# Acquisition-System_HMI_V1_0.net
KiCad netlist of a schematic drawn in Altium Designer
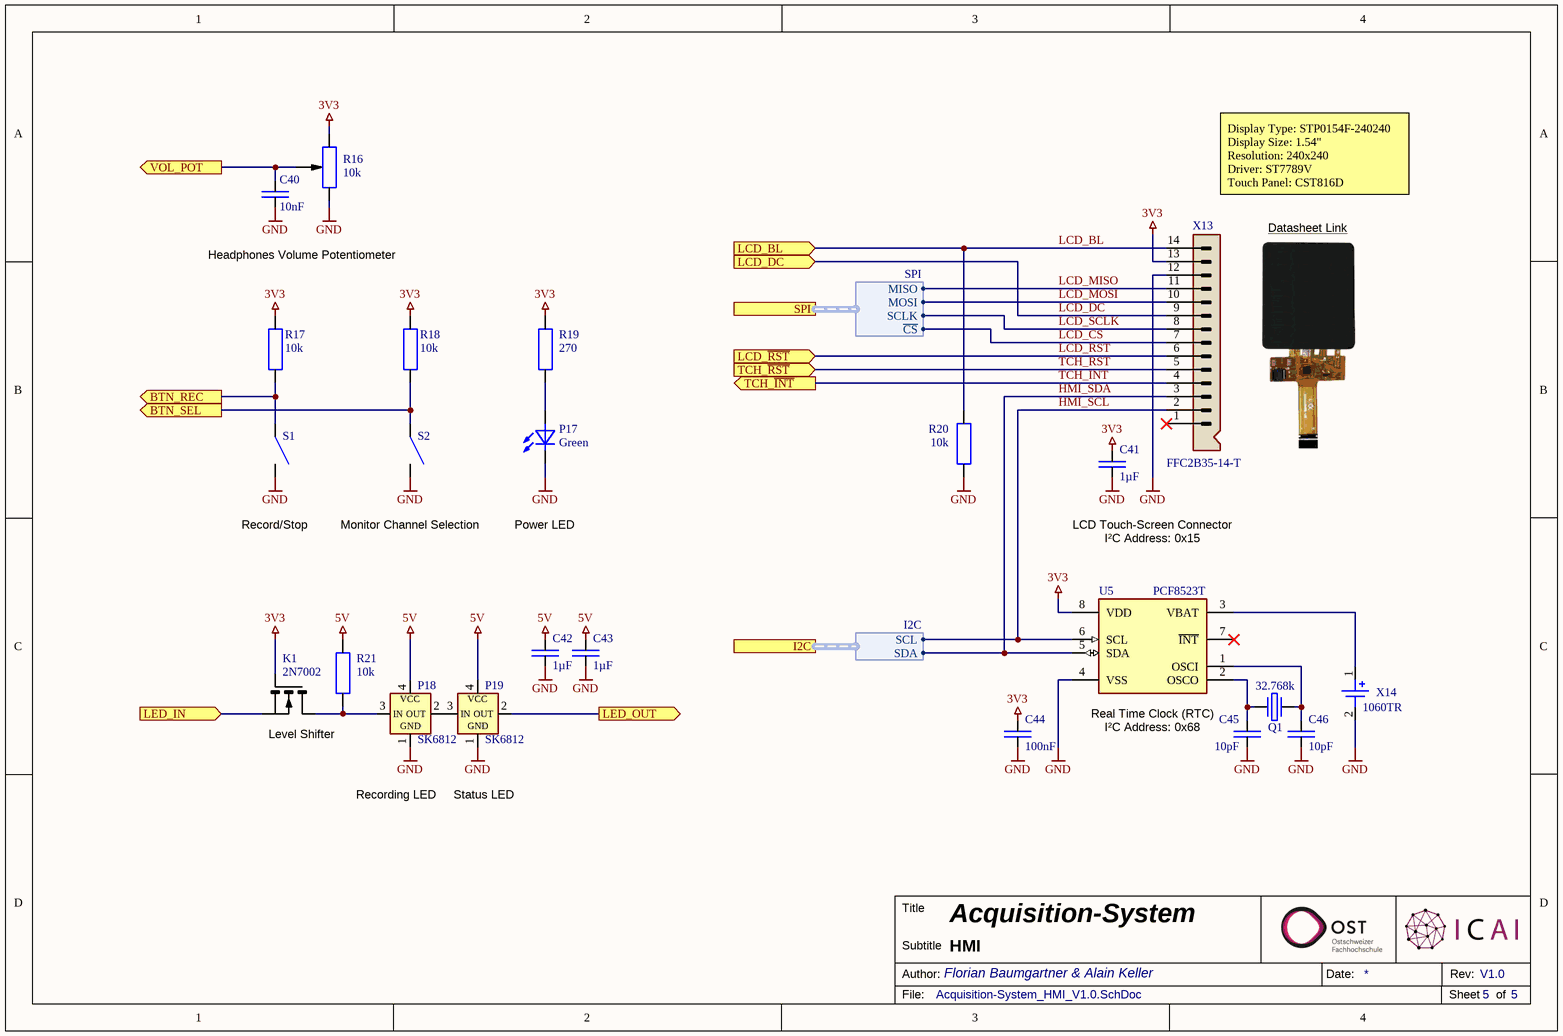
[diagram p0: Acquisition-System_HMI_V1.0.SchDoc]

(export (version "E")
  (design (tool "Eeschema 10.0.6"))
  (components
    (comp (ref "C40")
      (value "10nF")
      (footprint "SMD Keramikkondensator 0603")
      (description "CAP-MK")
      (libsource (lib "AudioAmp") (part "C-CAPACITOR"))
    )
    (comp (ref "C41")
      (value "1µF")
      (footprint "SMD Keramikkondensator 0603")
      (description "CAP-MK")
      (libsource (lib "AudioAmp") (part "C-CAPACITOR"))
    )
    (comp (ref "C42")
      (value "1µF")
      (footprint "SMD Keramikkondensator 0603")
      (description "CAP-MK")
      (libsource (lib "AudioAmp") (part "C-CAPACITOR"))
    )
    (comp (ref "C43")
      (value "1µF")
      (footprint "SMD Keramikkondensator 0603")
      (description "CAP-MK")
      (libsource (lib "AudioAmp") (part "C-CAPACITOR"))
    )
    (comp (ref "C44")
      (value "100nF")
      (footprint "SMD Keramikkondensator 0603")
      (description "SMD Ceramic Capacitor E6")
      (libsource (lib "Ceramic Capacitors-E6") (part "E6 - 100nF"))
    )
    (comp (ref "C45")
      (value "10pF")
      (footprint "SMD Keramikkondensator 0603")
      (description "CAP-MK")
      (libsource (lib "AudioAmp") (part "C-CAPACITOR"))
    )
    (comp (ref "C46")
      (value "10pF")
      (footprint "SMD Keramikkondensator 0603")
      (description "CAP-MK")
      (libsource (lib "AudioAmp") (part "C-CAPACITOR"))
    )
    (comp (ref "K1")
      (value "2N7002")
      (footprint "SMD MOSFET SOT-23")
      (description "MOSFET N-Channel")
      (libsource (lib "Nixie-Test") (part "K-FET{colon}NIGE"))
    )
    (comp (ref "P17")
      (value "Green")
      (footprint "SMD LED 0603")
      (description "General Purpose LED")
      (libsource (lib "Fleet-Monitor") (part "LED Green 0603"))
    )
    (comp (ref "P18")
      (value "SK6812")
      (footprint "SMD LED WS2812B-3528")
      (description "Smart RGB-LED")
      (libsource (lib "Acquisition-System") (part "P-SK6812D-EC3210R"))
    )
    (comp (ref "P19")
      (value "SK6812")
      (footprint "SMD LED WS2812B-3528")
      (description "Smart RGB-LED")
      (libsource (lib "Acquisition-System") (part "P-SK6812D-EC3210R"))
    )
    (comp (ref "Q1") (value "32.768k") (libsource (lib "Acquisition-System") (part "Q-Crystal")))
    (comp (ref "R16")
      (value "10k")
      (footprint "THT Potentiometer (RK09D1130C2P)")
      (description "RES-VAR")
      (libsource (lib "Acquisition-System") (part "R-RES{colon}VAR"))
    )
    (comp (ref "R17")
      (value "10k")
      (footprint "SMD Widerstand 0603")
      (description "RES (E=Heizwiderstand B=Messwandler)")
      (libsource (lib "TFS Integrated Library") (part "R-RESISTOR"))
    )
    (comp (ref "R18")
      (value "10k")
      (footprint "SMD Widerstand 0603")
      (description "RES (E=Heizwiderstand B=Messwandler)")
      (libsource (lib "TFS Integrated Library") (part "R-RESISTOR"))
    )
    (comp (ref "R19")
      (value "270")
      (footprint "SMD Widerstand 0603")
      (description "SMD-Widerstand 1/4W")
      (libsource (lib "Backplane_1") (part "R-RESISTOR"))
    )
    (comp (ref "R20")
      (value "10k")
      (footprint "SMD Widerstand 0603")
      (description "RES (E=Heizwiderstand B=Messwandler)")
      (libsource (lib "TFS Integrated Library") (part "R-RESISTOR"))
    )
    (comp (ref "R21")
      (value "10k")
      (footprint "SMD Widerstand 0603")
      (description "RES (E=Heizwiderstand B=Messwandler)")
      (libsource (lib "TFS Integrated Library") (part "R-RESISTOR"))
    )
    (comp (ref "S1")
      (value "SMD-Button")
      (footprint "SMD Button 4.2x3.2x2.5")
      (description "Button SPST")
      (libsource (lib "Switches") (part "Button 3mmx2.5mm"))
    )
    (comp (ref "S2")
      (value "SMD-Button")
      (footprint "SMD Button 4.2x3.2x2.5")
      (description "Button SPST")
      (libsource (lib "Switches") (part "Button 3mmx2.5mm"))
    )
    (comp (ref "U5")
      (value "PCF8523T")
      (footprint "SMD IC TO-263-5")
      (description "Real-Time Clock (RTC) and Calendar")
      (libsource (lib "Acquisition-System") (part "U-PCF8523T"))
    )
    (comp (ref "X13")
      (value "FFC2B35-14-T")
      (footprint "THT Pin-Header 1x6 (NP)")
      (description "FPC-Connector (14-Pin, Front Flip,  Bottom Contact)")
      (libsource (lib "Acquisition-System") (part "X-FPC-Connector (14-Pin)"))
    )
    (comp (ref "X14")
      (value "1060TR")
      (footprint "SMD Battery-Holder (1048P)")
      (description "Battery Holder (CR2032)")
      (libsource (lib "Acquisition-System") (part "X-CR2032-Battery-Holder"))
    )
  )
  (nets
    (net (code "3") (name "/BTN_REC") (class "Default")
      (node (ref "R17") (pin "1") (pinfunction "1_1") (pintype "passive"))
      (node (ref "S1") (pin "1") (pinfunction "1_1") (pintype "passive"))
    )
    (net (code "4") (name "/BTN_SEL") (class "Default")
      (node (ref "R18") (pin "1") (pinfunction "1_1") (pintype "passive"))
      (node (ref "S2") (pin "1") (pinfunction "1_1") (pintype "passive"))
    )
    (net (code "5") (name "/HMI_SCL") (class "Default")
      (node (ref "U5") (pin "6") (pinfunction "SCL_6") (pintype "input"))
      (node (ref "X13") (pin "2") (pinfunction "2_2") (pintype "passive"))
    )
    (net (code "6") (name "/HMI_SDA") (class "Default")
      (node (ref "U5") (pin "5") (pinfunction "SDA_5") (pintype "bidirectional"))
      (node (ref "X13") (pin "3") (pinfunction "3_3") (pintype "passive"))
    )
    (net (code "7") (name "/LCD_BL") (class "Default")
      (node (ref "R20") (pin "2") (pinfunction "2_2") (pintype "passive"))
      (node (ref "X13") (pin "14") (pinfunction "14_14") (pintype "passive"))
    )
    (net (code "8") (name "/LCD_DC") (class "Default")
      (node (ref "X13") (pin "9") (pinfunction "9_9") (pintype "passive"))
    )
    (net (code "9") (name "/LCD_MISO") (class "Default")
      (node (ref "X13") (pin "11") (pinfunction "11_11") (pintype "passive"))
    )
    (net (code "10") (name "/LCD_MOSI") (class "Default")
      (node (ref "X13") (pin "10") (pinfunction "10_10") (pintype "passive"))
    )
    (net (code "11") (name "/LCD_SCLK") (class "Default")
      (node (ref "X13") (pin "8") (pinfunction "8_8") (pintype "passive"))
    )
    (net (code "12") (name "/LCD_~{CS}") (class "Default")
      (node (ref "X13") (pin "7") (pinfunction "7_7") (pintype "passive"))
    )
    (net (code "13") (name "/LCD_~{RST}") (class "Default")
      (node (ref "X13") (pin "6") (pinfunction "6_6") (pintype "passive"))
    )
    (net (code "14") (name "/LED_IN") (class "Default")
      (node (ref "K1") (pin "S") (pinfunction "S_S") (pintype "passive"))
    )
    (net (code "15") (name "/LED_OUT") (class "Default")
      (node (ref "P19") (pin "2") (pinfunction "OUT_2") (pintype "passive"))
    )
    (net (code "16") (name "/TCH_~{INT}") (class "Default")
      (node (ref "X13") (pin "4") (pinfunction "4_4") (pintype "passive"))
    )
    (net (code "17") (name "/TCH_~{RST}") (class "Default")
      (node (ref "X13") (pin "5") (pinfunction "5_5") (pintype "passive"))
    )
    (net (code "18") (name "/VOL_POT") (class "Default")
      (node (ref "C40") (pin "2") (pinfunction "2_2") (pintype "passive"))
      (node (ref "R16") (pin "M") (pinfunction "M_M") (pintype "passive"))
    )
    (net (code "21") (name "3V3") (class "Default")
      (node (ref "C41") (pin "2") (pinfunction "2_2") (pintype "passive"))
      (node (ref "C44") (pin "2") (pinfunction "2_2") (pintype "passive"))
      (node (ref "K1") (pin "G") (pinfunction "G_G") (pintype "passive"))
      (node (ref "R16") (pin "CCW") (pinfunction "CCW_CCW") (pintype "passive"))
      (node (ref "R17") (pin "2") (pinfunction "2_2") (pintype "passive"))
      (node (ref "R18") (pin "2") (pinfunction "2_2") (pintype "passive"))
      (node (ref "R19") (pin "1") (pinfunction "1_1") (pintype "passive"))
      (node (ref "U5") (pin "8") (pinfunction "VDD_8") (pintype "power_in"))
      (node (ref "X13") (pin "13") (pinfunction "13_13") (pintype "passive"))
    )
    (net (code "22") (name "5V") (class "Default")
      (node (ref "C42") (pin "2") (pinfunction "2_2") (pintype "passive"))
      (node (ref "C43") (pin "2") (pinfunction "2_2") (pintype "passive"))
      (node (ref "P18") (pin "4") (pinfunction "VCC_4") (pintype "power_in"))
      (node (ref "P19") (pin "4") (pinfunction "VCC_4") (pintype "power_in"))
      (node (ref "R21") (pin "2") (pinfunction "2_2") (pintype "passive"))
    )
    (net (code "23") (name "GND") (class "Default")
      (node (ref "C40") (pin "1") (pinfunction "1_1") (pintype "passive"))
      (node (ref "C41") (pin "1") (pinfunction "1_1") (pintype "passive"))
      (node (ref "C42") (pin "1") (pinfunction "1_1") (pintype "passive"))
      (node (ref "C43") (pin "1") (pinfunction "1_1") (pintype "passive"))
      (node (ref "C44") (pin "1") (pinfunction "1_1") (pintype "passive"))
      (node (ref "C45") (pin "2") (pinfunction "2_2") (pintype "passive"))
      (node (ref "C46") (pin "2") (pinfunction "2_2") (pintype "passive"))
      (node (ref "P17") (pin "K") (pinfunction "K_K") (pintype "passive"))
      (node (ref "P18") (pin "1") (pinfunction "GND_1") (pintype "power_in"))
      (node (ref "P19") (pin "1") (pinfunction "GND_1") (pintype "power_in"))
      (node (ref "R16") (pin "CW") (pinfunction "CW_CW") (pintype "passive"))
      (node (ref "R20") (pin "1") (pinfunction "1_1") (pintype "passive"))
      (node (ref "S1") (pin "2") (pinfunction "2_2") (pintype "passive"))
      (node (ref "S2") (pin "2") (pinfunction "2_2") (pintype "passive"))
      (node (ref "U5") (pin "4") (pinfunction "VSS_4") (pintype "power_in"))
      (node (ref "X13") (pin "12") (pinfunction "12_12") (pintype "passive"))
      (node (ref "X14") (pin "2") (pinfunction "N_2") (pintype "passive"))
    )
    (net (code "24") (name "Net-(P17-PadA)") (class "Default")
      (node (ref "P17") (pin "A") (pinfunction "A_A") (pintype "passive"))
      (node (ref "R19") (pin "2") (pinfunction "2_2") (pintype "passive"))
    )
    (net (code "25") (name "Net-(P18-IN)") (class "Default")
      (node (ref "K1") (pin "D") (pinfunction "D_D") (pintype "passive"))
      (node (ref "P18") (pin "3") (pinfunction "IN_3") (pintype "passive"))
      (node (ref "R21") (pin "1") (pinfunction "1_1") (pintype "passive"))
    )
    (net (code "26") (name "Net-(P18-OUT)") (class "Default")
      (node (ref "P18") (pin "2") (pinfunction "OUT_2") (pintype "passive"))
      (node (ref "P19") (pin "3") (pinfunction "IN_3") (pintype "passive"))
    )
    (net (code "27") (name "Net-(U5-OSCI)") (class "Default")
      (node (ref "C46") (pin "1") (pinfunction "1_1") (pintype "passive"))
      (node (ref "Q1") (pin "2") (pinfunction "2_2") (pintype "passive"))
      (node (ref "U5") (pin "1") (pinfunction "OSCI_1") (pintype "passive"))
    )
    (net (code "28") (name "Net-(U5-OSCO)") (class "Default")
      (node (ref "C45") (pin "1") (pinfunction "1_1") (pintype "passive"))
      (node (ref "Q1") (pin "1") (pinfunction "1_1") (pintype "passive"))
      (node (ref "U5") (pin "2") (pinfunction "OSCO_2") (pintype "passive"))
    )
    (net (code "29") (name "Net-(U5-VBAT)") (class "Default")
      (node (ref "U5") (pin "3") (pinfunction "VBAT_3") (pintype "power_in"))
      (node (ref "X14") (pin "1") (pinfunction "P_1") (pintype "passive"))
    )
    (net (code "30") (name "unconnected-(U5-NC-Pad9)") (class "Default")
      (node (ref "U5") (pin "9") (pinfunction "NC_9") (pintype "passive"))
    )
    (net (code "31") (name "unconnected-(U5-NC-Pad10)") (class "Default")
      (node (ref "U5") (pin "10") (pinfunction "NC_10") (pintype "passive"))
    )
    (net (code "32") (name "unconnected-(U5-NC-Pad11)") (class "Default")
      (node (ref "U5") (pin "11") (pinfunction "NC_11") (pintype "passive"))
    )
    (net (code "33") (name "unconnected-(U5-~{INT}-Pad7)") (class "Default")
      (node (ref "U5") (pin "7") (pinfunction "~{INT}_7") (pintype "open_collector+no_connect"))
    )
    (net (code "34") (name "unconnected-(X13-Pad1)") (class "Default")
      (node (ref "X13") (pin "1") (pinfunction "1_1") (pintype "passive+no_connect"))
    )
  )
)
